# copy_done.net
KiCad netlist of a schematic drawn in Altium Designer
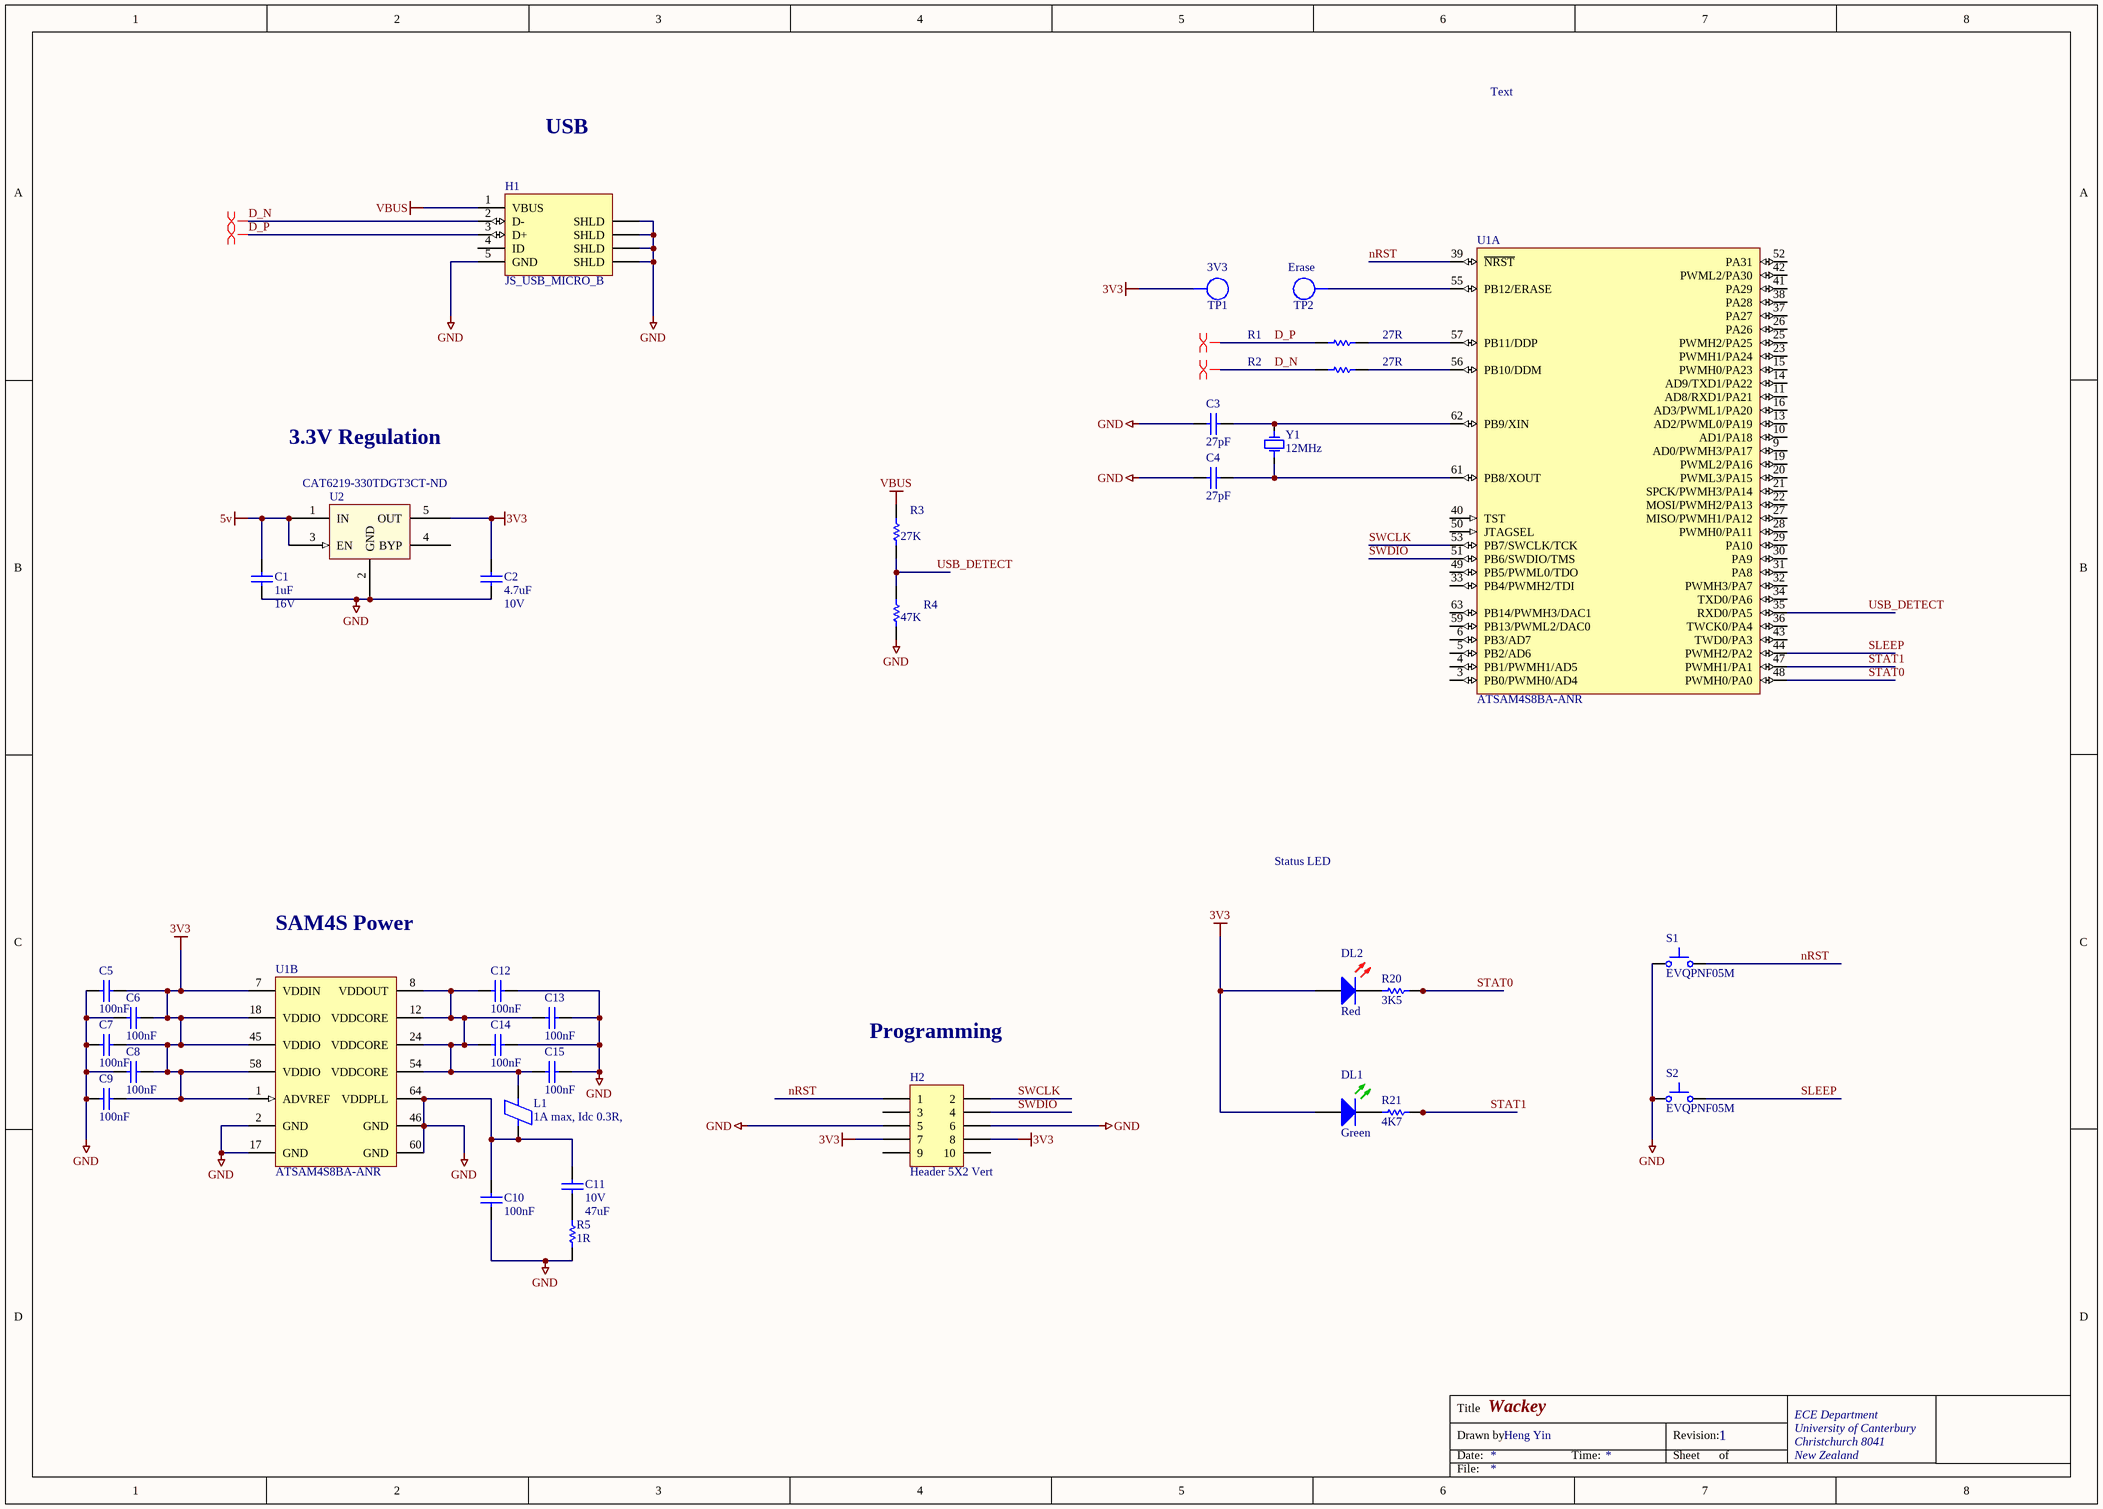
[diagram p0: copy_done.SchDoc]

(export (version "E")
  (design (tool "Eeschema 10.0.6"))
  (components
    (comp (ref "C1")
      (value "1uF")
      (footprint "CAPC1608L")
      (description "CAP CER 1uF Y5V -20% +80% 16V 0603")
      (fields (field (name "MAX VOLTAGE") "16V"))
      (libsource (lib "ECE AD19Components_22V1") (part "CC_1uF_0603"))
    )
    (comp (ref "C2")
      (value "4.7uF")
      (footprint "CAPC1608N")
      (description "CAP CER 4.7uF X5R +-20%  10V 0603")
      (fields (field (name "MAX VOLTAGE") "10V"))
      (libsource (lib "ECE AD19Components_22V1") (part "CC_4.7uF_0603"))
    )
    (comp (ref "C3")
      (value "27pF")
      (footprint "CAPC1608L")
      (description "CAP CER 27pF NPO/COG +-5% 50V 0603")
      (libsource (lib "ECE AD19Components_22V1") (part "CC_27pF_0603"))
    )
    (comp (ref "C4")
      (value "27pF")
      (footprint "CAPC1608L")
      (description "CAP CER 27pF NPO/COG +-5% 50V 0603")
      (libsource (lib "ECE AD19Components_22V1") (part "CC_27pF_0603"))
    )
    (comp (ref "C5")
      (value "100nF")
      (footprint "CAPC1608L")
      (description "CAP CER 100nF X7R +-10% 50V 0603")
      (libsource (lib "ECE AD19Components_22V1") (part "CC_100nF_0603"))
    )
    (comp (ref "C6")
      (value "100nF")
      (footprint "CAPC1608L")
      (description "CAP CER 100nF X7R +-10% 50V 0603")
      (libsource (lib "ECE AD19Components_22V1") (part "CC_100nF_0603"))
    )
    (comp (ref "C7")
      (value "100nF")
      (footprint "CAPC1608L")
      (description "CAP CER 100nF X7R +-10% 50V 0603")
      (libsource (lib "ECE AD19Components_22V1") (part "CC_100nF_0603"))
    )
    (comp (ref "C8")
      (value "100nF")
      (footprint "CAPC1608L")
      (description "CAP CER 100nF X7R +-10% 50V 0603")
      (libsource (lib "ECE AD19Components_22V1") (part "CC_100nF_0603"))
    )
    (comp (ref "C9")
      (value "100nF")
      (footprint "CAPC1608L")
      (description "CAP CER 100nF X7R +-10% 50V 0603")
      (libsource (lib "ECE AD19Components_22V1") (part "CC_100nF_0603"))
    )
    (comp (ref "C10")
      (value "100nF")
      (footprint "CAPC1608L")
      (description "CAP CER 100nF X7R +-10% 50V 0603")
      (libsource (lib "ECE AD19Components_22V1") (part "CC_100nF_0603"))
    )
    (comp (ref "C11")
      (value "47uF")
      (footprint "CAPC3216L")
      (description "CAP CER 47uF X5R -/+20% 10V 1206")
      (fields (field (name "MAX VOLTAGE") "10V"))
      (libsource (lib "ECE AD19Components_22V1") (part "CC_47uF_1206"))
    )
    (comp (ref "C12")
      (value "100nF")
      (footprint "CAPC1608L")
      (description "CAP CER 100nF X7R +-10% 50V 0603")
      (libsource (lib "ECE AD19Components_22V1") (part "CC_100nF_0603"))
    )
    (comp (ref "C13")
      (value "100nF")
      (footprint "CAPC1608L")
      (description "CAP CER 100nF X7R +-10% 50V 0603")
      (libsource (lib "ECE AD19Components_22V1") (part "CC_100nF_0603"))
    )
    (comp (ref "C14")
      (value "100nF")
      (footprint "CAPC1608L")
      (description "CAP CER 100nF X7R +-10% 50V 0603")
      (libsource (lib "ECE AD19Components_22V1") (part "CC_100nF_0603"))
    )
    (comp (ref "C15")
      (value "100nF")
      (footprint "CAPC1608L")
      (description "CAP CER 100nF X7R +-10% 50V 0603")
      (libsource (lib "ECE AD19Components_22V1") (part "CC_100nF_0603"))
    )
    (comp (ref "DL1")
      (value "Green")
      (footprint "WL-SMCW0603")
      (description "LED Green 430mcd 0603 SMD")
      (fields
        (field (name "MANUFACTURER") "WURTH ELEKTRONIK")
        (field (name "MANUFACTURER PART NUMBER") "150060GS75000")
        (field (name "LED COLOUR") "Green")
      )
      (libsource (lib "ECE AD19Components_22V1") (part "DL_150060GS75000"))
    )
    (comp (ref "DL2")
      (value "Red")
      (footprint "WL-SMCW0603")
      (description "LED Red 250mcd 0603 SMD")
      (fields
        (field (name "MANUFACTURER") "WURTH ELEKTRONIK")
        (field (name "MANUFACTURER PART NUMBER") "150060RS75000")
        (field (name "LED COLOUR") "Red")
      )
      (libsource (lib "ECE AD19Components_22V1") (part "DL_150060RS75000"))
    )
    (comp (ref "H1")
      (value "JS_USB_MICRO_B")
      (footprint "FCI_USB_10118194-0001LF")
      (description "CONN USB MICRO B RECPT SMT R/A")
      (fields (field (name "MANUFACTURER") "FCI") (field (name "MANUFACTURER PART NUMBER") "10118194-0001LF"))
      (libsource (lib "ECE AD19Components_22V1") (part "JS_USB_MICRO_B_SMT"))
    )
    (comp (ref "H2")
      (value "Header 5X2 Vert")
      (footprint "IDC2.54-V10D")
      (description "IDC Header, 2,54mm, 10-Pin, Vert")
      (libsource (lib "ECE AD19Components_22V1") (part "JA_HDR_IDC_5X2_VERT"))
    )
    (comp (ref "L1")
      (value "1A max, Idc 0.3R,")
      (footprint "INDC3216L")
      (description "Ferrite Bead, Rdc 0.3R, Z100MHZ 600R, Imax 1A, SMD 1206")
      (fields
        (field (name "MANUFACTURER") "FAIR-RITE")
        (field (name "MANUFACTURER PART NUMBER") "2512066017Y1")
      )
      (libsource (lib "ECE AD19Components_22V1") (part "IN_Ferrite-Bead"))
    )
    (comp (ref "R1")
      (value "27R")
      (footprint "RESC1608L")
      (description "RES 27 OHM 1/10W 5% 0603 SMD")
      (libsource (lib "ECE AD19Components_22V1") (part "RS_27R"))
    )
    (comp (ref "R2")
      (value "27R")
      (footprint "RESC1608L")
      (description "RES 27 OHM 1/10W 5% 0603 SMD")
      (libsource (lib "ECE AD19Components_22V1") (part "RS_27R"))
    )
    (comp (ref "R3")
      (value "27K")
      (footprint "RESC1608L")
      (description "RES 27K OHM 1/10W 5% 0603 SMD")
      (libsource (lib "ECE AD19Components_22V1") (part "RS_27K"))
    )
    (comp (ref "R4")
      (value "47K")
      (footprint "RESC1608N")
      (description "RES 47.0K OHM 1/10W 5% 0603 SMD")
      (libsource (lib "ECE AD19Components_22V1") (part "RS_47K"))
    )
    (comp (ref "R5")
      (value "1R")
      (footprint "RESC3216L")
      (description "RES 1R OHM 1/4W 5% 1206 SMD")
      (libsource (lib "ECE AD19Components_22V1") (part "RT_1R"))
    )
    (comp (ref "R20")
      (value "3K5")
      (footprint "RESC1608L")
      (description "RES 4.7K OHM 1/10W 5% 0603 SMD")
      (libsource (lib "ECE AD19Components_22V1") (part "RS_4K7"))
    )
    (comp (ref "R21")
      (value "4K7")
      (footprint "RESC1608L")
      (description "RES 4.7K OHM 1/10W 5% 0603 SMD")
      (libsource (lib "ECE AD19Components_22V1") (part "RS_4K7"))
    )
    (comp (ref "S1")
      (value "EVQPNF05M")
      (footprint "EVQPNF05M")
      (description "Panasonic 6 x 3.5mm SMD Light Touch Switch Type SMD")
      (fields (field (name "MANUFACTURER") "Panasonic"))
      (libsource (lib "ECE AD19Components_22V1") (part "WS_EVQPNF05M"))
    )
    (comp (ref "S2")
      (value "EVQPNF05M")
      (footprint "EVQPNF05M")
      (description "Panasonic 6 x 3.5mm SMD Light Touch Switch Type SMD")
      (fields (field (name "MANUFACTURER") "Panasonic"))
      (libsource (lib "ECE AD19Components_22V1") (part "WS_EVQPNF05M"))
    )
    (comp (ref "TP1")
      (value "TP")
      (footprint "TP_1206")
      (description "Test-Point 3.3x1.6x2.1mm SMD")
      (fields
        (field (name "MANUFACTURER") "Harwin Inc")
        (field (name "MANUFACTURER PART NUMBER") "S1751-46R")
      )
      (libsource (lib "ECE AD19Components_22V1") (part "TP_1206"))
    )
    (comp (ref "TP2")
      (value "TP")
      (footprint "TP_1206")
      (description "Test-Point 3.3x1.6x2.1mm SMD")
      (fields
        (field (name "MANUFACTURER") "Harwin Inc")
        (field (name "MANUFACTURER PART NUMBER") "S1751-46R")
      )
      (libsource (lib "ECE AD19Components_22V1") (part "TP_1206"))
    )
    (comp (ref "U1")
      (value "ATSAM4S8BA-ANR")
      (footprint "LQFP64_L")
      (description "IC MCU 32BIT 512KB FLASH 64LQFP")
      (fields (field (name "MANUFACTURER") "Atmel"))
      (libsource (lib "ECE AD19Components_22V1") (part "SE_ATSAM4S16BA-MU"))
    )
    (comp (ref "U2")
      (value "CAT6219-330TDGT3")
      (footprint "SOT95P280X145-5N")
      (description "IC REG LIN 3.3V 500MA TSOT23-5")
      (fields
        (field (name "BASE PART NUMBER") "CAT6219")
        (field (name "SUPPLIER PART NUMBER") "CAT6219-330TDGT3CT-ND")
      )
      (libsource (lib "ENCE461AD19_V23") (part "SV_CAT6219-330TDGT3"))
    )
    (comp (ref "Y1")
      (value "12MHz")
      (footprint "6.0X3.5-4")
      (description "CRYSTAL 12MHZ 18PF 6X3.5mm SMD")
      (fields
        (field (name "MANUFACTURER") "CTS-Frequency Controls")
        (field (name "MANUFACTURER PART NUMBER") "406C35D12M00000")
        (field (name "FREQUENCY") "12MHz")
      )
      (libsource (lib "ECE AD19Components_22V1") (part "XT_CRYSTAL_12MHz_18pF"))
    )
  )
  (nets
    (net (code "1") (name "/D_N") (class "Default")
      (node (ref "H1") (pin "2") (pinfunction "D-_2") (pintype "bidirectional"))
      (node (ref "R2") (pin "1") (pinfunction "1_1") (pintype "passive"))
    )
    (net (code "2") (name "/D_P") (class "Default")
      (node (ref "H1") (pin "3") (pinfunction "D+_3") (pintype "bidirectional"))
      (node (ref "R1") (pin "1") (pinfunction "1_1") (pintype "passive"))
    )
    (net (code "3") (name "/SLEEP") (class "Default")
      (node (ref "S2") (pin "2") (pintype "passive"))
      (node (ref "U1") (pin "44") (pinfunction "PWMH2/PA2_44") (pintype "bidirectional"))
    )
    (net (code "4") (name "/STAT0") (class "Default")
      (node (ref "R20") (pin "2") (pinfunction "2_2") (pintype "passive"))
      (node (ref "U1") (pin "48") (pinfunction "PWMH0/PA0_48") (pintype "bidirectional"))
    )
    (net (code "5") (name "/STAT1") (class "Default")
      (node (ref "R21") (pin "2") (pinfunction "2_2") (pintype "passive"))
      (node (ref "U1") (pin "47") (pinfunction "PWMH1/PA1_47") (pintype "bidirectional"))
    )
    (net (code "6") (name "/SWCLK") (class "Default")
      (node (ref "H2") (pin "2") (pinfunction "2_2") (pintype "passive"))
      (node (ref "U1") (pin "53") (pinfunction "PB7/SWCLK/TCK_53") (pintype "bidirectional"))
    )
    (net (code "7") (name "/SWDIO") (class "Default")
      (node (ref "H2") (pin "4") (pinfunction "4_4") (pintype "passive"))
      (node (ref "U1") (pin "51") (pinfunction "PB6/SWDIO/TMS_51") (pintype "bidirectional"))
    )
    (net (code "8") (name "/USB_DETECT") (class "Default")
      (node (ref "R3") (pin "1") (pinfunction "1_1") (pintype "passive"))
      (node (ref "R4") (pin "2") (pinfunction "2_2") (pintype "passive"))
      (node (ref "U1") (pin "35") (pinfunction "RXD0/PA5_35") (pintype "bidirectional"))
    )
    (net (code "9") (name "/nRST") (class "Default")
      (node (ref "H2") (pin "1") (pinfunction "1_1") (pintype "passive"))
      (node (ref "S1") (pin "2") (pintype "passive"))
      (node (ref "U1") (pin "39") (pinfunction "~{NRST}_39") (pintype "bidirectional"))
    )
    (net (code "10") (name "3V3") (class "Default")
      (node (ref "C2") (pin "2") (pinfunction "2_2") (pintype "passive"))
      (node (ref "C5") (pin "2") (pinfunction "2_2") (pintype "passive"))
      (node (ref "C6") (pin "2") (pinfunction "2_2") (pintype "passive"))
      (node (ref "C7") (pin "2") (pinfunction "2_2") (pintype "passive"))
      (node (ref "C8") (pin "2") (pinfunction "2_2") (pintype "passive"))
      (node (ref "C9") (pin "1") (pinfunction "1_1") (pintype "passive"))
      (node (ref "DL1") (pin "2") (pinfunction "A_2") (pintype "passive"))
      (node (ref "DL2") (pin "2") (pinfunction "A_2") (pintype "passive"))
      (node (ref "H2") (pin "7") (pinfunction "7_7") (pintype "passive"))
      (node (ref "H2") (pin "8") (pinfunction "8_8") (pintype "passive"))
      (node (ref "TP1") (pin "1") (pinfunction "1_1") (pintype "passive"))
      (node (ref "U1") (pin "1") (pinfunction "ADVREF_1") (pintype "input"))
      (node (ref "U1") (pin "18") (pinfunction "VDDIO_18") (pintype "power_in"))
      (node (ref "U1") (pin "45") (pinfunction "VDDIO_45") (pintype "power_in"))
      (node (ref "U1") (pin "58") (pinfunction "VDDIO_58") (pintype "power_in"))
      (node (ref "U1") (pin "7") (pinfunction "VDDIN_7") (pintype "power_in"))
      (node (ref "U2") (pin "5") (pinfunction "OUT_5") (pintype "power_in"))
    )
    (net (code "11") (name "5v") (class "Default")
      (node (ref "C1") (pin "2") (pinfunction "2_2") (pintype "passive"))
      (node (ref "U2") (pin "1") (pinfunction "IN_1") (pintype "power_in"))
      (node (ref "U2") (pin "3") (pinfunction "EN_3") (pintype "input"))
    )
    (net (code "12") (name "GND") (class "Default")
      (node (ref "C1") (pin "1") (pinfunction "1_1") (pintype "passive"))
      (node (ref "C10") (pin "1") (pinfunction "1_1") (pintype "passive"))
      (node (ref "C10") (pin "2") (pinfunction "2_2") (pintype "passive"))
      (node (ref "C11") (pin "2") (pinfunction "2_2") (pintype "passive"))
      (node (ref "C12") (pin "2") (pinfunction "2_2") (pintype "passive"))
      (node (ref "C13") (pin "2") (pinfunction "2_2") (pintype "passive"))
      (node (ref "C14") (pin "2") (pinfunction "2_2") (pintype "passive"))
      (node (ref "C15") (pin "2") (pinfunction "2_2") (pintype "passive"))
      (node (ref "C2") (pin "1") (pinfunction "1_1") (pintype "passive"))
      (node (ref "C3") (pin "1") (pinfunction "1_1") (pintype "passive"))
      (node (ref "C4") (pin "1") (pinfunction "1_1") (pintype "passive"))
      (node (ref "C5") (pin "1") (pinfunction "1_1") (pintype "passive"))
      (node (ref "C6") (pin "1") (pinfunction "1_1") (pintype "passive"))
      (node (ref "C7") (pin "1") (pinfunction "1_1") (pintype "passive"))
      (node (ref "C8") (pin "1") (pinfunction "1_1") (pintype "passive"))
      (node (ref "C9") (pin "2") (pinfunction "2_2") (pintype "passive"))
      (node (ref "H1") (pin "5") (pinfunction "GND_5") (pintype "passive"))
      (node (ref "H1") (pin "6") (pinfunction "SHLD_6") (pintype "passive"))
      (node (ref "H2") (pin "5") (pinfunction "5_5") (pintype "passive"))
      (node (ref "H2") (pin "6") (pinfunction "6_6") (pintype "passive"))
      (node (ref "L1") (pin "1") (pinfunction "1_1") (pintype "passive"))
      (node (ref "R4") (pin "1") (pinfunction "1_1") (pintype "passive"))
      (node (ref "R5") (pin "1") (pinfunction "1_1") (pintype "passive"))
      (node (ref "S1") (pin "1") (pintype "passive"))
      (node (ref "S2") (pin "1") (pintype "passive"))
      (node (ref "U1") (pin "17") (pinfunction "GND_17") (pintype "power_in"))
      (node (ref "U1") (pin "2") (pinfunction "GND_2") (pintype "power_in"))
      (node (ref "U1") (pin "46") (pinfunction "GND_46") (pintype "power_in"))
      (node (ref "U1") (pin "60") (pinfunction "GND_60") (pintype "power_in"))
      (node (ref "U1") (pin "64") (pinfunction "VDDPLL_64") (pintype "power_in"))
      (node (ref "U2") (pin "2") (pinfunction "GND_2") (pintype "power_in"))
    )
    (net (code "13") (name "Net-(C11-Pad1)") (class "Default")
      (node (ref "C11") (pin "1") (pinfunction "1_1") (pintype "passive"))
      (node (ref "R5") (pin "2") (pinfunction "2_2") (pintype "passive"))
    )
    (net (code "14") (name "Net-(U1A-PB8{slash}XOUT)") (class "Default")
      (node (ref "C4") (pin "2") (pinfunction "2_2") (pintype "passive"))
      (node (ref "U1") (pin "61") (pinfunction "PB8/XOUT_61") (pintype "bidirectional"))
      (node (ref "Y1") (pin "1") (pinfunction "OSC1_1") (pintype "passive"))
    )
    (net (code "15") (name "Net-(U1A-PB9{slash}XIN)") (class "Default")
      (node (ref "C3") (pin "2") (pinfunction "2_2") (pintype "passive"))
      (node (ref "U1") (pin "62") (pinfunction "PB9/XIN_62") (pintype "bidirectional"))
      (node (ref "Y1") (pin "3") (pinfunction "OSC2_3") (pintype "passive"))
    )
    (net (code "16") (name "Net-(U1A-PB10{slash}DDM)") (class "Default")
      (node (ref "R2") (pin "2") (pinfunction "2_2") (pintype "passive"))
      (node (ref "U1") (pin "56") (pinfunction "PB10/DDM_56") (pintype "bidirectional"))
    )
    (net (code "17") (name "Net-(U1A-PB11{slash}DDP)") (class "Default")
      (node (ref "R1") (pin "2") (pinfunction "2_2") (pintype "passive"))
      (node (ref "U1") (pin "57") (pinfunction "PB11/DDP_57") (pintype "bidirectional"))
    )
    (net (code "18") (name "Net-(U1A-PB12{slash}ERASE)") (class "Default")
      (node (ref "TP2") (pin "1") (pinfunction "1_1") (pintype "passive"))
      (node (ref "U1") (pin "55") (pinfunction "PB12/ERASE_55") (pintype "bidirectional"))
    )
    (net (code "19") (name "Net-(U1B-VDDOUT)") (class "Default")
      (node (ref "C12") (pin "1") (pinfunction "1_1") (pintype "passive"))
      (node (ref "C13") (pin "1") (pinfunction "1_1") (pintype "passive"))
      (node (ref "C14") (pin "1") (pinfunction "1_1") (pintype "passive"))
      (node (ref "C15") (pin "1") (pinfunction "1_1") (pintype "passive"))
      (node (ref "L1") (pin "2") (pinfunction "2_2") (pintype "passive"))
      (node (ref "U1") (pin "12") (pinfunction "VDDCORE_12") (pintype "power_in"))
      (node (ref "U1") (pin "24") (pinfunction "VDDCORE_24") (pintype "power_in"))
      (node (ref "U1") (pin "54") (pinfunction "VDDCORE_54") (pintype "power_in"))
      (node (ref "U1") (pin "8") (pinfunction "VDDOUT_8") (pintype "power_in"))
    )
    (net (code "20") (name "VBUS") (class "Default")
      (node (ref "H1") (pin "1") (pinfunction "VBUS_1") (pintype "power_in"))
      (node (ref "R3") (pin "2") (pinfunction "2_2") (pintype "passive"))
    )
    (net (code "21") (name "unconnected-(DL1-K-Pad1)") (class "Default")
      (node (ref "DL1") (pin "1") (pinfunction "K_1") (pintype "passive"))
    )
    (net (code "22") (name "unconnected-(DL2-K-Pad1)") (class "Default")
      (node (ref "DL2") (pin "1") (pinfunction "K_1") (pintype "passive"))
    )
    (net (code "23") (name "unconnected-(H1-ID-Pad4)") (class "Default")
      (node (ref "H1") (pin "4") (pinfunction "ID_4") (pintype "power_in"))
    )
    (net (code "24") (name "unconnected-(H2-Pad3)") (class "Default")
      (node (ref "H2") (pin "3") (pinfunction "3_3") (pintype "passive"))
    )
    (net (code "25") (name "unconnected-(H2-Pad9)") (class "Default")
      (node (ref "H2") (pin "9") (pinfunction "9_9") (pintype "passive"))
    )
    (net (code "26") (name "unconnected-(H2-Pad10)") (class "Default")
      (node (ref "H2") (pin "10") (pinfunction "10_10") (pintype "passive"))
    )
    (net (code "27") (name "unconnected-(R20-Pad1)") (class "Default")
      (node (ref "R20") (pin "1") (pinfunction "1_1") (pintype "passive"))
    )
    (net (code "28") (name "unconnected-(R21-Pad1)") (class "Default")
      (node (ref "R21") (pin "1") (pinfunction "1_1") (pintype "passive"))
    )
    (net (code "29") (name "unconnected-(U1A-AD0{slash}PWMH3{slash}PA17-Pad9)") (class "Default")
      (node (ref "U1") (pin "9") (pinfunction "AD0/PWMH3/PA17_9") (pintype "bidirectional"))
    )
    (net (code "30") (name "unconnected-(U1A-AD1{slash}PA18-Pad10)") (class "Default")
      (node (ref "U1") (pin "10") (pinfunction "AD1/PA18_10") (pintype "bidirectional"))
    )
    (net (code "31") (name "unconnected-(U1A-AD2{slash}PWML0{slash}PA19-Pad13)") (class "Default")
      (node (ref "U1") (pin "13") (pinfunction "AD2/PWML0/PA19_13") (pintype "bidirectional"))
    )
    (net (code "32") (name "unconnected-(U1A-AD3{slash}PWML1{slash}PA20-Pad16)") (class "Default")
      (node (ref "U1") (pin "16") (pinfunction "AD3/PWML1/PA20_16") (pintype "bidirectional"))
    )
    (net (code "33") (name "unconnected-(U1A-AD8{slash}RXD1{slash}PA21-Pad11)") (class "Default")
      (node (ref "U1") (pin "11") (pinfunction "AD8/RXD1/PA21_11") (pintype "bidirectional"))
    )
    (net (code "34") (name "unconnected-(U1A-AD9{slash}TXD1{slash}PA22-Pad14)") (class "Default")
      (node (ref "U1") (pin "14") (pinfunction "AD9/TXD1/PA22_14") (pintype "bidirectional"))
    )
    (net (code "35") (name "unconnected-(U1A-JTAGSEL-Pad50)") (class "Default")
      (node (ref "U1") (pin "50") (pinfunction "JTAGSEL_50") (pintype "input"))
    )
    (net (code "36") (name "unconnected-(U1A-MISO{slash}PWMH1{slash}PA12-Pad27)") (class "Default")
      (node (ref "U1") (pin "27") (pinfunction "MISO/PWMH1/PA12_27") (pintype "bidirectional"))
    )
    (net (code "37") (name "unconnected-(U1A-MOSI{slash}PWMH2{slash}PA13-Pad22)") (class "Default")
      (node (ref "U1") (pin "22") (pinfunction "MOSI/PWMH2/PA13_22") (pintype "bidirectional"))
    )
    (net (code "38") (name "unconnected-(U1A-PA8-Pad31)") (class "Default")
      (node (ref "U1") (pin "31") (pinfunction "PA8_31") (pintype "bidirectional"))
    )
    (net (code "39") (name "unconnected-(U1A-PA9-Pad30)") (class "Default")
      (node (ref "U1") (pin "30") (pinfunction "PA9_30") (pintype "bidirectional"))
    )
    (net (code "40") (name "unconnected-(U1A-PA10-Pad29)") (class "Default")
      (node (ref "U1") (pin "29") (pinfunction "PA10_29") (pintype "bidirectional"))
    )
    (net (code "41") (name "unconnected-(U1A-PA26-Pad26)") (class "Default")
      (node (ref "U1") (pin "26") (pinfunction "PA26_26") (pintype "bidirectional"))
    )
    (net (code "42") (name "unconnected-(U1A-PA27-Pad37)") (class "Default")
      (node (ref "U1") (pin "37") (pinfunction "PA27_37") (pintype "bidirectional"))
    )
    (net (code "43") (name "unconnected-(U1A-PA28-Pad38)") (class "Default")
      (node (ref "U1") (pin "38") (pinfunction "PA28_38") (pintype "bidirectional"))
    )
    (net (code "44") (name "unconnected-(U1A-PA29-Pad41)") (class "Default")
      (node (ref "U1") (pin "41") (pinfunction "PA29_41") (pintype "bidirectional"))
    )
    (net (code "45") (name "unconnected-(U1A-PA31-Pad52)") (class "Default")
      (node (ref "U1") (pin "52") (pinfunction "PA31_52") (pintype "bidirectional"))
    )
    (net (code "46") (name "unconnected-(U1A-PB0{slash}PWMH0{slash}AD4-Pad3)") (class "Default")
      (node (ref "U1") (pin "3") (pinfunction "PB0/PWMH0/AD4_3") (pintype "bidirectional"))
    )
    (net (code "47") (name "unconnected-(U1A-PB1{slash}PWMH1{slash}AD5-Pad4)") (class "Default")
      (node (ref "U1") (pin "4") (pinfunction "PB1/PWMH1/AD5_4") (pintype "bidirectional"))
    )
    (net (code "48") (name "unconnected-(U1A-PB2{slash}AD6-Pad5)") (class "Default")
      (node (ref "U1") (pin "5") (pinfunction "PB2/AD6_5") (pintype "bidirectional"))
    )
    (net (code "49") (name "unconnected-(U1A-PB3{slash}AD7-Pad6)") (class "Default")
      (node (ref "U1") (pin "6") (pinfunction "PB3/AD7_6") (pintype "bidirectional"))
    )
    (net (code "50") (name "unconnected-(U1A-PB4{slash}PWMH2{slash}TDI-Pad33)") (class "Default")
      (node (ref "U1") (pin "33") (pinfunction "PB4/PWMH2/TDI_33") (pintype "bidirectional"))
    )
    (net (code "51") (name "unconnected-(U1A-PB5{slash}PWML0{slash}TDO-Pad49)") (class "Default")
      (node (ref "U1") (pin "49") (pinfunction "PB5/PWML0/TDO_49") (pintype "bidirectional"))
    )
    (net (code "52") (name "unconnected-(U1A-PB13{slash}PWML2{slash}DAC0-Pad59)") (class "Default")
      (node (ref "U1") (pin "59") (pinfunction "PB13/PWML2/DAC0_59") (pintype "bidirectional"))
    )
    (net (code "53") (name "unconnected-(U1A-PB14{slash}PWMH3{slash}DAC1-Pad63)") (class "Default")
      (node (ref "U1") (pin "63") (pinfunction "PB14/PWMH3/DAC1_63") (pintype "bidirectional"))
    )
    (net (code "54") (name "unconnected-(U1A-PWMH0{slash}PA11-Pad28)") (class "Default")
      (node (ref "U1") (pin "28") (pinfunction "PWMH0/PA11_28") (pintype "bidirectional"))
    )
    (net (code "55") (name "unconnected-(U1A-PWMH0{slash}PA23-Pad15)") (class "Default")
      (node (ref "U1") (pin "15") (pinfunction "PWMH0/PA23_15") (pintype "bidirectional"))
    )
    (net (code "56") (name "unconnected-(U1A-PWMH1{slash}PA24-Pad23)") (class "Default")
      (node (ref "U1") (pin "23") (pinfunction "PWMH1/PA24_23") (pintype "bidirectional"))
    )
    (net (code "57") (name "unconnected-(U1A-PWMH2{slash}PA25-Pad25)") (class "Default")
      (node (ref "U1") (pin "25") (pinfunction "PWMH2/PA25_25") (pintype "bidirectional"))
    )
    (net (code "58") (name "unconnected-(U1A-PWMH3{slash}PA7-Pad32)") (class "Default")
      (node (ref "U1") (pin "32") (pinfunction "PWMH3/PA7_32") (pintype "bidirectional"))
    )
    (net (code "59") (name "unconnected-(U1A-PWML2{slash}PA16-Pad19)") (class "Default")
      (node (ref "U1") (pin "19") (pinfunction "PWML2/PA16_19") (pintype "bidirectional"))
    )
    (net (code "60") (name "unconnected-(U1A-PWML2{slash}PA30-Pad42)") (class "Default")
      (node (ref "U1") (pin "42") (pinfunction "PWML2/PA30_42") (pintype "bidirectional"))
    )
    (net (code "61") (name "unconnected-(U1A-PWML3{slash}PA15-Pad20)") (class "Default")
      (node (ref "U1") (pin "20") (pinfunction "PWML3/PA15_20") (pintype "bidirectional"))
    )
    (net (code "62") (name "unconnected-(U1A-SPCK{slash}PWMH3{slash}PA14-Pad21)") (class "Default")
      (node (ref "U1") (pin "21") (pinfunction "SPCK/PWMH3/PA14_21") (pintype "bidirectional"))
    )
    (net (code "63") (name "unconnected-(U1A-TST-Pad40)") (class "Default")
      (node (ref "U1") (pin "40") (pinfunction "TST_40") (pintype "input"))
    )
    (net (code "64") (name "unconnected-(U1A-TWCK0{slash}PA4-Pad36)") (class "Default")
      (node (ref "U1") (pin "36") (pinfunction "TWCK0/PA4_36") (pintype "bidirectional"))
    )
    (net (code "65") (name "unconnected-(U1A-TWD0{slash}PA3-Pad43)") (class "Default")
      (node (ref "U1") (pin "43") (pinfunction "TWD0/PA3_43") (pintype "bidirectional"))
    )
    (net (code "66") (name "unconnected-(U1A-TXD0{slash}PA6-Pad34)") (class "Default")
      (node (ref "U1") (pin "34") (pinfunction "TXD0/PA6_34") (pintype "bidirectional"))
    )
    (net (code "67") (name "unconnected-(U2-BYP-Pad4)") (class "Default")
      (node (ref "U2") (pin "4") (pinfunction "BYP_4") (pintype "passive"))
    )
  )
)
